# Buzzer_Block.net
KiCad netlist of a schematic drawn in Altium Designer
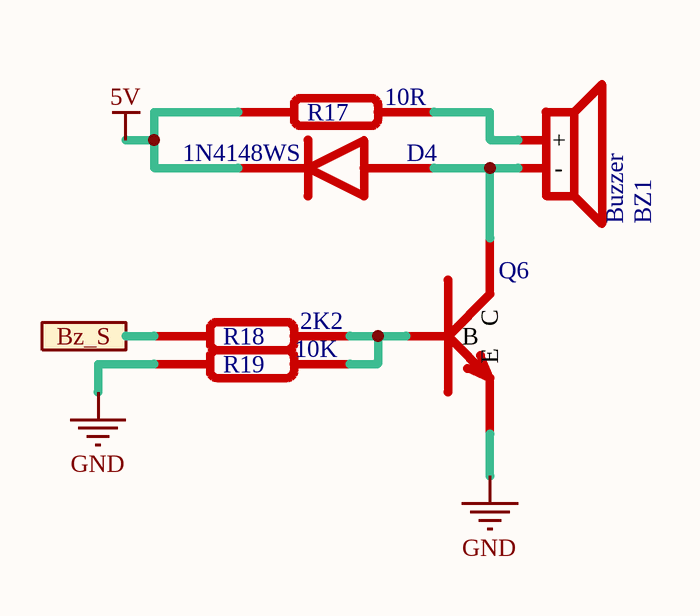
[diagram p0: Buzzer_Block.SchDoc]

(export (version "E")
  (design (tool "Eeschema 10.0.6"))
  (components
    (comp (ref "BZ1")
      (value "Buzzer")
      (footprint "AST0927MW-03TRQ")
      (description "Voltage Rate 5V, Current 50mA")
      (libsource (lib "CTAI-Library") (part "Buzzer"))
    )
    (comp (ref "D4")
      (value "1N4148WS")
      (footprint "SMA")
      (description "Small Signal Diode")
      (libsource (lib "CTAI-Library") (part "1N4148WS"))
    )
    (comp (ref "Q6")
      (value "S8050")
      (footprint "SOT-23")
      (description "NPN Transistors 0.5A Collector to Emitter 25V")
      (libsource (lib "CTAI-Library") (part "S8050"))
    )
    (comp (ref "R17")
      (value "10R")
      (footprint "R0603")
      (description "Resistor")
      (libsource (lib "CTAI-Library") (part "Resistor"))
    )
    (comp (ref "R18")
      (value "2K2")
      (footprint "R0603")
      (description "Resistor")
      (libsource (lib "CTAI-Library") (part "Resistor"))
    )
    (comp (ref "R19")
      (value "10K")
      (footprint "R0603")
      (description "Resistor")
      (libsource (lib "CTAI-Library") (part "Resistor"))
    )
  )
  (nets
    (net (code "1") (name "/Bz_S") (class "Default")
      (node (ref "R18") (pin "2") (pinfunction "2_2") (pintype "passive"))
    )
    (net (code "2") (name "5V") (class "Default")
      (node (ref "D4") (pin "K") (pinfunction "K_K") (pintype "passive"))
      (node (ref "R17") (pin "2") (pinfunction "2_2") (pintype "passive"))
    )
    (net (code "3") (name "GND") (class "Default")
      (node (ref "Q6") (pin "2") (pinfunction "E_2") (pintype "passive"))
      (node (ref "R19") (pin "2") (pinfunction "2_2") (pintype "passive"))
    )
    (net (code "4") (name "Net-(BZ1-+)") (class "Default")
      (node (ref "BZ1") (pin "1") (pinfunction "+_1") (pintype "passive"))
      (node (ref "R17") (pin "1") (pinfunction "1_1") (pintype "passive"))
    )
    (net (code "5") (name "Net-(BZ1--)") (class "Default")
      (node (ref "BZ1") (pin "2") (pinfunction "-_2") (pintype "passive"))
      (node (ref "D4") (pin "A") (pinfunction "A_A") (pintype "passive"))
      (node (ref "Q6") (pin "3") (pinfunction "C_3") (pintype "passive"))
    )
    (net (code "6") (name "Net-(Q6-B)") (class "Default")
      (node (ref "Q6") (pin "1") (pinfunction "B_1") (pintype "passive"))
      (node (ref "R18") (pin "1") (pinfunction "1_1") (pintype "passive"))
      (node (ref "R19") (pin "1") (pinfunction "1_1") (pintype "passive"))
    )
  )
)
